# PCB-BI8-1x8SC3.net
KiCad netlist of a schematic drawn in EAGLE
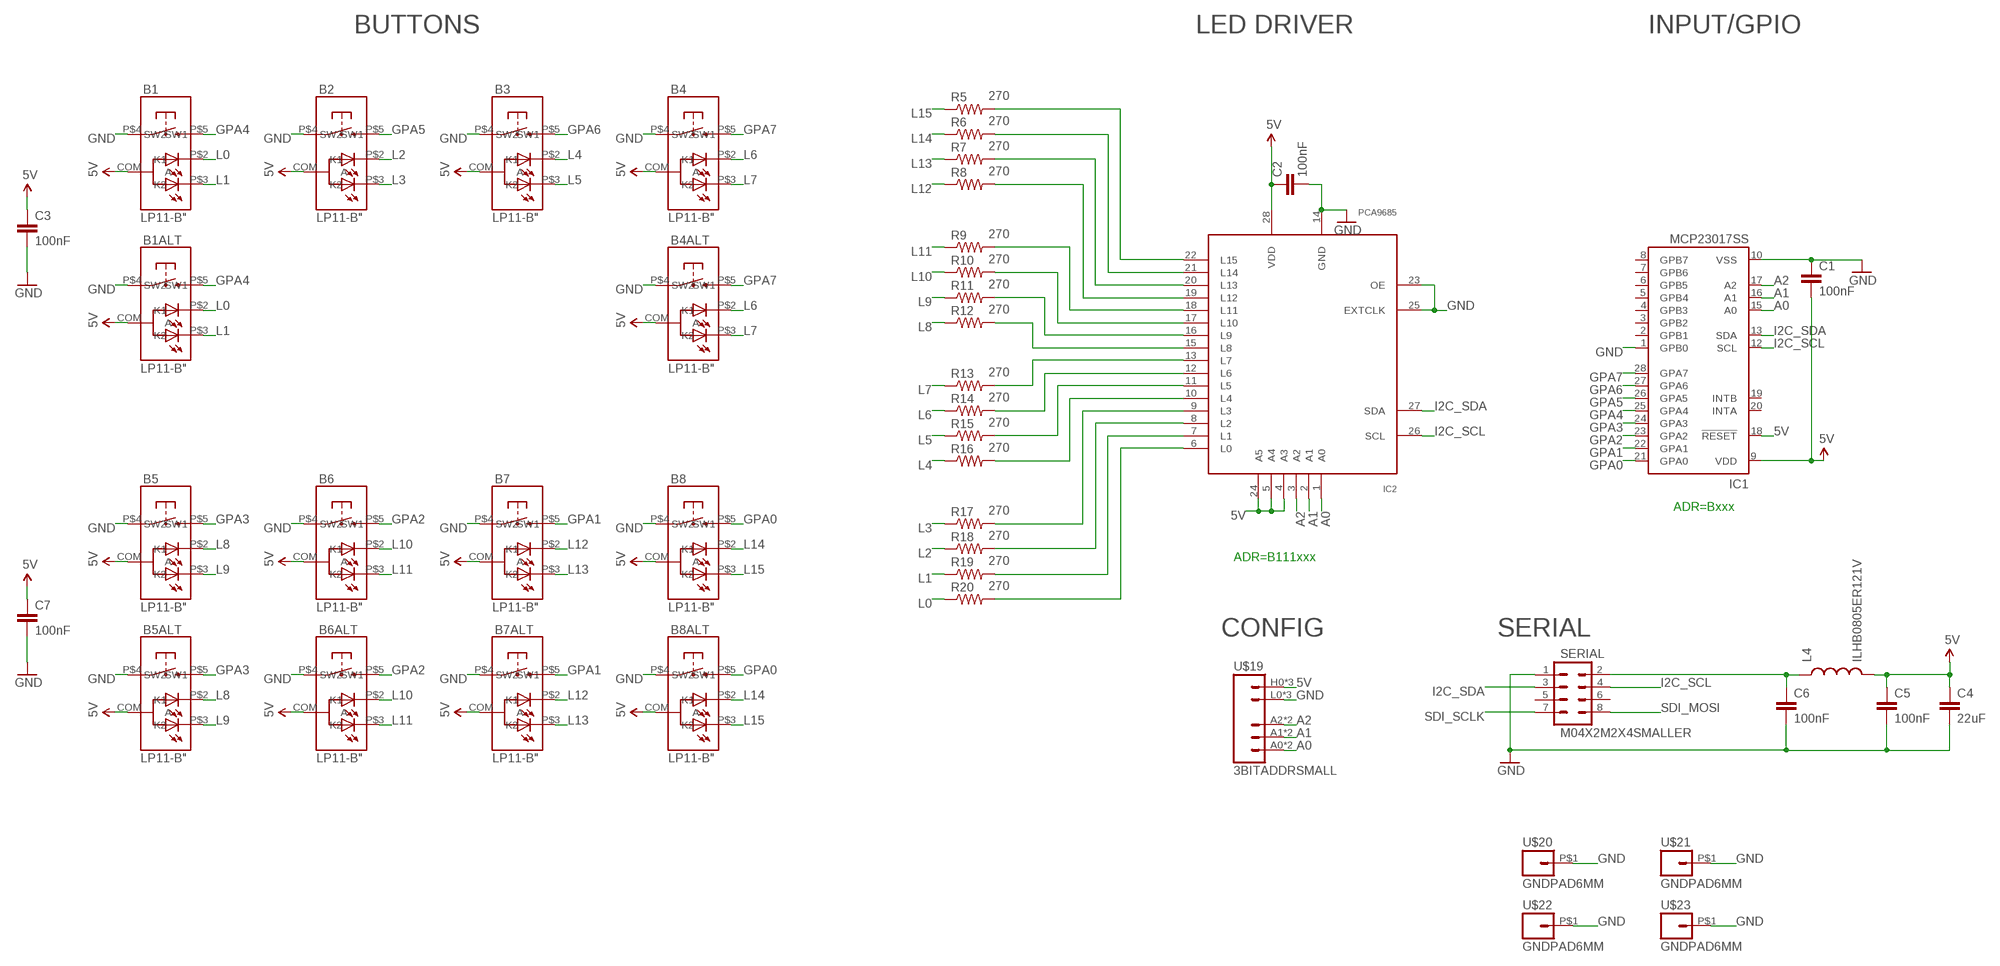
[diagram p0: schematic, sheet 1]

(export (version "E")
  (design (tool "Eeschema 10.0.6"))
  (components
    (comp (ref "B1")
      (value "LP11-B\"")
      (footprint "eagle-import:LP11")
      (libsource (lib "eagle-import") (part "LP11-B{dblquote}"))
    )
    (comp (ref "B1ALT")
      (value "LP11-B\"")
      (footprint "eagle-import:LP11")
      (libsource (lib "eagle-import") (part "LP11-B{dblquote}"))
    )
    (comp (ref "B2")
      (value "LP11-B\"")
      (footprint "eagle-import:LP11")
      (libsource (lib "eagle-import") (part "LP11-B{dblquote}"))
    )
    (comp (ref "B3")
      (value "LP11-B\"")
      (footprint "eagle-import:LP11")
      (libsource (lib "eagle-import") (part "LP11-B{dblquote}"))
    )
    (comp (ref "B4")
      (value "LP11-B\"")
      (footprint "eagle-import:LP11")
      (libsource (lib "eagle-import") (part "LP11-B{dblquote}"))
    )
    (comp (ref "B4ALT")
      (value "LP11-B\"")
      (footprint "eagle-import:LP11")
      (libsource (lib "eagle-import") (part "LP11-B{dblquote}"))
    )
    (comp (ref "B5")
      (value "LP11-B\"")
      (footprint "eagle-import:LP11")
      (libsource (lib "eagle-import") (part "LP11-B{dblquote}"))
    )
    (comp (ref "B5ALT")
      (value "LP11-B\"")
      (footprint "eagle-import:LP11")
      (libsource (lib "eagle-import") (part "LP11-B{dblquote}"))
    )
    (comp (ref "B6")
      (value "LP11-B\"")
      (footprint "eagle-import:LP11")
      (libsource (lib "eagle-import") (part "LP11-B{dblquote}"))
    )
    (comp (ref "B6ALT")
      (value "LP11-B\"")
      (footprint "eagle-import:LP11")
      (libsource (lib "eagle-import") (part "LP11-B{dblquote}"))
    )
    (comp (ref "B7")
      (value "LP11-B\"")
      (footprint "eagle-import:LP11")
      (libsource (lib "eagle-import") (part "LP11-B{dblquote}"))
    )
    (comp (ref "B7ALT")
      (value "LP11-B\"")
      (footprint "eagle-import:LP11")
      (libsource (lib "eagle-import") (part "LP11-B{dblquote}"))
    )
    (comp (ref "B8")
      (value "LP11-B\"")
      (footprint "eagle-import:LP11")
      (libsource (lib "eagle-import") (part "LP11-B{dblquote}"))
    )
    (comp (ref "B8ALT")
      (value "LP11-B\"")
      (footprint "eagle-import:LP11")
      (libsource (lib "eagle-import") (part "LP11-B{dblquote}"))
    )
    (comp (ref "C1")
      (value "100nF")
      (footprint "eagle-import:0603-CAP")
      (libsource (lib "eagle-import") (part "CAP0603-CAP"))
    )
    (comp (ref "C2")
      (value "100nF")
      (footprint "eagle-import:0603-CAP")
      (libsource (lib "eagle-import") (part "CAP0603-CAP"))
    )
    (comp (ref "C3")
      (value "100nF")
      (footprint "eagle-import:0603-CAP")
      (libsource (lib "eagle-import") (part "CAP0603-CAP"))
    )
    (comp (ref "C4")
      (value "22uF")
      (footprint "eagle-import:0805")
      (libsource (lib "eagle-import") (part "CAP0805"))
    )
    (comp (ref "C5")
      (value "100nF")
      (footprint "eagle-import:0603-CAP")
      (libsource (lib "eagle-import") (part "CAP0603-CAP"))
    )
    (comp (ref "C6")
      (value "100nF")
      (footprint "eagle-import:0603-CAP")
      (libsource (lib "eagle-import") (part "CAP0603-CAP"))
    )
    (comp (ref "C7")
      (value "100nF")
      (footprint "eagle-import:0603-CAP")
      (libsource (lib "eagle-import") (part "CAP0603-CAP"))
    )
    (comp (ref "IC1")
      (value "MCP23017SS")
      (footprint "eagle-import:SSOP28")
      (fields
        (field (name "MF") "MICROCHIP")
        (field (name "MPN") "MCP23017-E/SS")
        (field (name "MPN_1") "MCP23017-E/SS")
        (field (name "OC_FARNELL") "1467674")
        (field (name "OC_NEWARK") "31K2960")
      )
      (libsource (lib "eagle-import") (part "MCP23017SS"))
    )
    (comp (ref "IC2")
      (value "PCA9685")
      (footprint "eagle-import:TSSOP28")
      (libsource (lib "eagle-import") (part "PCA9685"))
    )
    (comp (ref "L4")
      (value "ILHB0805ER121V")
      (footprint "eagle-import:0805")
      (libsource (lib "eagle-import") (part "INDUCTOR0805"))
    )
    (comp (ref "R5")
      (value "270")
      (footprint "eagle-import:0603-RES")
      (libsource (lib "eagle-import") (part "RESISTOR0603-RES"))
    )
    (comp (ref "R6")
      (value "270")
      (footprint "eagle-import:0603-RES")
      (libsource (lib "eagle-import") (part "RESISTOR0603-RES"))
    )
    (comp (ref "R7")
      (value "270")
      (footprint "eagle-import:0603-RES")
      (libsource (lib "eagle-import") (part "RESISTOR0603-RES"))
    )
    (comp (ref "R8")
      (value "270")
      (footprint "eagle-import:0603-RES")
      (libsource (lib "eagle-import") (part "RESISTOR0603-RES"))
    )
    (comp (ref "R9")
      (value "270")
      (footprint "eagle-import:0603-RES")
      (libsource (lib "eagle-import") (part "RESISTOR0603-RES"))
    )
    (comp (ref "R10")
      (value "270")
      (footprint "eagle-import:0603-RES")
      (libsource (lib "eagle-import") (part "RESISTOR0603-RES"))
    )
    (comp (ref "R11")
      (value "270")
      (footprint "eagle-import:0603-RES")
      (libsource (lib "eagle-import") (part "RESISTOR0603-RES"))
    )
    (comp (ref "R12")
      (value "270")
      (footprint "eagle-import:0603-RES")
      (libsource (lib "eagle-import") (part "RESISTOR0603-RES"))
    )
    (comp (ref "R13")
      (value "270")
      (footprint "eagle-import:0603-RES")
      (libsource (lib "eagle-import") (part "RESISTOR0603-RES"))
    )
    (comp (ref "R14")
      (value "270")
      (footprint "eagle-import:0603-RES")
      (libsource (lib "eagle-import") (part "RESISTOR0603-RES"))
    )
    (comp (ref "R15")
      (value "270")
      (footprint "eagle-import:0603-RES")
      (libsource (lib "eagle-import") (part "RESISTOR0603-RES"))
    )
    (comp (ref "R16")
      (value "270")
      (footprint "eagle-import:0603-RES")
      (libsource (lib "eagle-import") (part "RESISTOR0603-RES"))
    )
    (comp (ref "R17")
      (value "270")
      (footprint "eagle-import:0603-RES")
      (libsource (lib "eagle-import") (part "RESISTOR0603-RES"))
    )
    (comp (ref "R18")
      (value "270")
      (footprint "eagle-import:0603-RES")
      (libsource (lib "eagle-import") (part "RESISTOR0603-RES"))
    )
    (comp (ref "R19")
      (value "270")
      (footprint "eagle-import:0603-RES")
      (libsource (lib "eagle-import") (part "RESISTOR0603-RES"))
    )
    (comp (ref "R20")
      (value "270")
      (footprint "eagle-import:0603-RES")
      (libsource (lib "eagle-import") (part "RESISTOR0603-RES"))
    )
    (comp (ref "SERIAL")
      (value "M04X2M2X4SMALLER")
      (footprint "eagle-import:M2X4SMALLER")
      (libsource (lib "eagle-import") (part "M04X2M2X4SMALLER"))
    )
    (comp (ref "U$19")
      (value "3BITADDRSMALL")
      (footprint "eagle-import:3BITADDR_SMALL")
      (libsource (lib "eagle-import") (part "3BITADDRSMALL"))
    )
    (comp (ref "U$20")
      (value "GNDPAD6MM")
      (footprint "eagle-import:3.2MMPAD6MM")
      (libsource (lib "eagle-import") (part "GNDPAD6MM"))
    )
    (comp (ref "U$21")
      (value "GNDPAD6MM")
      (footprint "eagle-import:3.2MMPAD6MM")
      (libsource (lib "eagle-import") (part "GNDPAD6MM"))
    )
    (comp (ref "U$22")
      (value "GNDPAD6MM")
      (footprint "eagle-import:3.2MMPAD6MM")
      (libsource (lib "eagle-import") (part "GNDPAD6MM"))
    )
    (comp (ref "U$23")
      (value "GNDPAD6MM")
      (footprint "eagle-import:3.2MMPAD6MM")
      (libsource (lib "eagle-import") (part "GNDPAD6MM"))
    )
  )
  (nets
    (net (code "1") (name "/A0") (class "Default")
      (node (ref "IC1") (pin "15") (pinfunction "A0_15") (pintype "input"))
      (node (ref "IC2") (pin "1") (pinfunction "A0_1") (pintype "input"))
      (node (ref "U$19") (pin "A0") (pinfunction "A0_A0") (pintype "passive"))
      (node (ref "U$19") (pin "AS0") (pinfunction "A0_AS0") (pintype "passive"))
    )
    (net (code "2") (name "/A1") (class "Default")
      (node (ref "IC1") (pin "16") (pinfunction "A1_16") (pintype "input"))
      (node (ref "IC2") (pin "2") (pinfunction "A1_2") (pintype "input"))
      (node (ref "U$19") (pin "A1") (pinfunction "A1_A1") (pintype "passive"))
      (node (ref "U$19") (pin "AS1") (pinfunction "A1_AS1") (pintype "passive"))
    )
    (net (code "3") (name "/A2") (class "Default")
      (node (ref "IC1") (pin "17") (pinfunction "A2_17") (pintype "input"))
      (node (ref "IC2") (pin "3") (pinfunction "A2_3") (pintype "input"))
      (node (ref "U$19") (pin "A2") (pinfunction "A2_A2") (pintype "passive"))
      (node (ref "U$19") (pin "AS2") (pinfunction "A2_AS2") (pintype "passive"))
    )
    (net (code "4") (name "/GPA0") (class "Default")
      (node (ref "B8") (pin "P$5") (pinfunction "SW2_P$5") (pintype "bidirectional"))
      (node (ref "B8ALT") (pin "P$5") (pinfunction "SW2_P$5") (pintype "bidirectional"))
      (node (ref "IC1") (pin "21") (pinfunction "GPA0_21") (pintype "bidirectional"))
    )
    (net (code "5") (name "/GPA1") (class "Default")
      (node (ref "B7") (pin "P$5") (pinfunction "SW2_P$5") (pintype "bidirectional"))
      (node (ref "B7ALT") (pin "P$5") (pinfunction "SW2_P$5") (pintype "bidirectional"))
      (node (ref "IC1") (pin "22") (pinfunction "GPA1_22") (pintype "bidirectional"))
    )
    (net (code "6") (name "/GPA2") (class "Default")
      (node (ref "B6") (pin "P$5") (pinfunction "SW2_P$5") (pintype "bidirectional"))
      (node (ref "B6ALT") (pin "P$5") (pinfunction "SW2_P$5") (pintype "bidirectional"))
      (node (ref "IC1") (pin "23") (pinfunction "GPA2_23") (pintype "bidirectional"))
    )
    (net (code "7") (name "/GPA3") (class "Default")
      (node (ref "B5") (pin "P$5") (pinfunction "SW2_P$5") (pintype "bidirectional"))
      (node (ref "B5ALT") (pin "P$5") (pinfunction "SW2_P$5") (pintype "bidirectional"))
      (node (ref "IC1") (pin "24") (pinfunction "GPA3_24") (pintype "bidirectional"))
    )
    (net (code "8") (name "/GPA4") (class "Default")
      (node (ref "B1") (pin "P$5") (pinfunction "SW2_P$5") (pintype "bidirectional"))
      (node (ref "B1ALT") (pin "P$5") (pinfunction "SW2_P$5") (pintype "bidirectional"))
      (node (ref "IC1") (pin "25") (pinfunction "GPA4_25") (pintype "bidirectional"))
    )
    (net (code "9") (name "/GPA5") (class "Default")
      (node (ref "B2") (pin "P$5") (pinfunction "SW2_P$5") (pintype "bidirectional"))
      (node (ref "IC1") (pin "26") (pinfunction "GPA5_26") (pintype "bidirectional"))
    )
    (net (code "10") (name "/GPA6") (class "Default")
      (node (ref "B3") (pin "P$5") (pinfunction "SW2_P$5") (pintype "bidirectional"))
      (node (ref "IC1") (pin "27") (pinfunction "GPA6_27") (pintype "bidirectional"))
    )
    (net (code "11") (name "/GPA7") (class "Default")
      (node (ref "B4") (pin "P$5") (pinfunction "SW2_P$5") (pintype "bidirectional"))
      (node (ref "B4ALT") (pin "P$5") (pinfunction "SW2_P$5") (pintype "bidirectional"))
      (node (ref "IC1") (pin "28") (pinfunction "GPA7_28") (pintype "bidirectional"))
    )
    (net (code "12") (name "/I2C_SCL") (class "Default")
      (node (ref "IC1") (pin "12") (pinfunction "SCL_12") (pintype "input"))
      (node (ref "IC2") (pin "26") (pinfunction "SCL_26") (pintype "input"))
      (node (ref "SERIAL") (pin "4") (pinfunction "4_4") (pintype "passive"))
    )
    (net (code "13") (name "/I2C_SDA") (class "Default")
      (node (ref "IC1") (pin "13") (pinfunction "SDA_13") (pintype "bidirectional"))
      (node (ref "IC2") (pin "27") (pinfunction "SDA_27") (pintype "input"))
      (node (ref "SERIAL") (pin "3") (pinfunction "3_3") (pintype "passive"))
    )
    (net (code "14") (name "/L0") (class "Default")
      (node (ref "B1") (pin "P$2") (pinfunction "K1_P$2") (pintype "bidirectional"))
      (node (ref "B1ALT") (pin "P$2") (pinfunction "K1_P$2") (pintype "bidirectional"))
      (node (ref "R20") (pin "1") (pinfunction "1_1") (pintype "passive"))
    )
    (net (code "15") (name "/L1") (class "Default")
      (node (ref "B1") (pin "P$3") (pinfunction "K2_P$3") (pintype "bidirectional"))
      (node (ref "B1ALT") (pin "P$3") (pinfunction "K2_P$3") (pintype "bidirectional"))
      (node (ref "R19") (pin "1") (pinfunction "1_1") (pintype "passive"))
    )
    (net (code "16") (name "/L2") (class "Default")
      (node (ref "B2") (pin "P$2") (pinfunction "K1_P$2") (pintype "bidirectional"))
      (node (ref "R18") (pin "1") (pinfunction "1_1") (pintype "passive"))
    )
    (net (code "17") (name "/L3") (class "Default")
      (node (ref "B2") (pin "P$3") (pinfunction "K2_P$3") (pintype "bidirectional"))
      (node (ref "R17") (pin "1") (pinfunction "1_1") (pintype "passive"))
    )
    (net (code "18") (name "/L4") (class "Default")
      (node (ref "B3") (pin "P$2") (pinfunction "K1_P$2") (pintype "bidirectional"))
      (node (ref "R16") (pin "1") (pinfunction "1_1") (pintype "passive"))
    )
    (net (code "19") (name "/L5") (class "Default")
      (node (ref "B3") (pin "P$3") (pinfunction "K2_P$3") (pintype "bidirectional"))
      (node (ref "R15") (pin "1") (pinfunction "1_1") (pintype "passive"))
    )
    (net (code "20") (name "/L6") (class "Default")
      (node (ref "B4") (pin "P$2") (pinfunction "K1_P$2") (pintype "bidirectional"))
      (node (ref "B4ALT") (pin "P$2") (pinfunction "K1_P$2") (pintype "bidirectional"))
      (node (ref "R14") (pin "1") (pinfunction "1_1") (pintype "passive"))
    )
    (net (code "21") (name "/L7") (class "Default")
      (node (ref "B4") (pin "P$3") (pinfunction "K2_P$3") (pintype "bidirectional"))
      (node (ref "B4ALT") (pin "P$3") (pinfunction "K2_P$3") (pintype "bidirectional"))
      (node (ref "R13") (pin "1") (pinfunction "1_1") (pintype "passive"))
    )
    (net (code "22") (name "/L8") (class "Default")
      (node (ref "B5") (pin "P$2") (pinfunction "K1_P$2") (pintype "bidirectional"))
      (node (ref "B5ALT") (pin "P$2") (pinfunction "K1_P$2") (pintype "bidirectional"))
      (node (ref "R12") (pin "1") (pinfunction "1_1") (pintype "passive"))
    )
    (net (code "23") (name "/L9") (class "Default")
      (node (ref "B5") (pin "P$3") (pinfunction "K2_P$3") (pintype "bidirectional"))
      (node (ref "B5ALT") (pin "P$3") (pinfunction "K2_P$3") (pintype "bidirectional"))
      (node (ref "R11") (pin "1") (pinfunction "1_1") (pintype "passive"))
    )
    (net (code "24") (name "/L10") (class "Default")
      (node (ref "B6") (pin "P$2") (pinfunction "K1_P$2") (pintype "bidirectional"))
      (node (ref "B6ALT") (pin "P$2") (pinfunction "K1_P$2") (pintype "bidirectional"))
      (node (ref "R10") (pin "1") (pinfunction "1_1") (pintype "passive"))
    )
    (net (code "25") (name "/L11") (class "Default")
      (node (ref "B6") (pin "P$3") (pinfunction "K2_P$3") (pintype "bidirectional"))
      (node (ref "B6ALT") (pin "P$3") (pinfunction "K2_P$3") (pintype "bidirectional"))
      (node (ref "R9") (pin "1") (pinfunction "1_1") (pintype "passive"))
    )
    (net (code "26") (name "/L12") (class "Default")
      (node (ref "B7") (pin "P$2") (pinfunction "K1_P$2") (pintype "bidirectional"))
      (node (ref "B7ALT") (pin "P$2") (pinfunction "K1_P$2") (pintype "bidirectional"))
      (node (ref "R8") (pin "1") (pinfunction "1_1") (pintype "passive"))
    )
    (net (code "27") (name "/L13") (class "Default")
      (node (ref "B7") (pin "P$3") (pinfunction "K2_P$3") (pintype "bidirectional"))
      (node (ref "B7ALT") (pin "P$3") (pinfunction "K2_P$3") (pintype "bidirectional"))
      (node (ref "R7") (pin "1") (pinfunction "1_1") (pintype "passive"))
    )
    (net (code "28") (name "/L14") (class "Default")
      (node (ref "B8") (pin "P$2") (pinfunction "K1_P$2") (pintype "bidirectional"))
      (node (ref "B8ALT") (pin "P$2") (pinfunction "K1_P$2") (pintype "bidirectional"))
      (node (ref "R6") (pin "1") (pinfunction "1_1") (pintype "passive"))
    )
    (net (code "29") (name "/L15") (class "Default")
      (node (ref "B8") (pin "P$3") (pinfunction "K2_P$3") (pintype "bidirectional"))
      (node (ref "B8ALT") (pin "P$3") (pinfunction "K2_P$3") (pintype "bidirectional"))
      (node (ref "R5") (pin "1") (pinfunction "1_1") (pintype "passive"))
    )
    (net (code "30") (name "/SDI_MOSI") (class "Default")
      (node (ref "SERIAL") (pin "8") (pinfunction "8_8") (pintype "passive"))
    )
    (net (code "31") (name "/SDI_SCLK") (class "Default")
      (node (ref "SERIAL") (pin "7") (pinfunction "7_7") (pintype "passive"))
    )
    (net (code "32") (name "5V") (class "Default")
      (node (ref "B1") (pin "COM") (pinfunction "A_COM") (pintype "bidirectional"))
      (node (ref "B1ALT") (pin "COM") (pinfunction "A_COM") (pintype "bidirectional"))
      (node (ref "B2") (pin "COM") (pinfunction "A_COM") (pintype "bidirectional"))
      (node (ref "B3") (pin "COM") (pinfunction "A_COM") (pintype "bidirectional"))
      (node (ref "B4") (pin "COM") (pinfunction "A_COM") (pintype "bidirectional"))
      (node (ref "B4ALT") (pin "COM") (pinfunction "A_COM") (pintype "bidirectional"))
      (node (ref "B5") (pin "COM") (pinfunction "A_COM") (pintype "bidirectional"))
      (node (ref "B5ALT") (pin "COM") (pinfunction "A_COM") (pintype "bidirectional"))
      (node (ref "B6") (pin "COM") (pinfunction "A_COM") (pintype "bidirectional"))
      (node (ref "B6ALT") (pin "COM") (pinfunction "A_COM") (pintype "bidirectional"))
      (node (ref "B7") (pin "COM") (pinfunction "A_COM") (pintype "bidirectional"))
      (node (ref "B7ALT") (pin "COM") (pinfunction "A_COM") (pintype "bidirectional"))
      (node (ref "B8") (pin "COM") (pinfunction "A_COM") (pintype "bidirectional"))
      (node (ref "B8ALT") (pin "COM") (pinfunction "A_COM") (pintype "bidirectional"))
      (node (ref "C1") (pin "2") (pinfunction "2_2") (pintype "passive"))
      (node (ref "C2") (pin "1") (pinfunction "1_1") (pintype "passive"))
      (node (ref "C3") (pin "1") (pinfunction "1_1") (pintype "passive"))
      (node (ref "C4") (pin "1") (pinfunction "1_1") (pintype "passive"))
      (node (ref "C5") (pin "1") (pinfunction "1_1") (pintype "passive"))
      (node (ref "C7") (pin "1") (pinfunction "1_1") (pintype "passive"))
      (node (ref "IC1") (pin "18") (pinfunction "~{RESET}_18") (pintype "input"))
      (node (ref "IC1") (pin "9") (pinfunction "VDD_9") (pintype "power_in"))
      (node (ref "IC2") (pin "24") (pinfunction "A5_24") (pintype "input"))
      (node (ref "IC2") (pin "28") (pinfunction "VDD_28") (pintype "power_in"))
      (node (ref "IC2") (pin "4") (pinfunction "A3_4") (pintype "input"))
      (node (ref "IC2") (pin "5") (pinfunction "A4_5") (pintype "input"))
      (node (ref "L4") (pin "2") (pinfunction "2_2") (pintype "passive"))
      (node (ref "U$19") (pin "H0") (pinfunction "VCC_H0") (pintype "passive"))
      (node (ref "U$19") (pin "H1") (pinfunction "VCC_H1") (pintype "passive"))
      (node (ref "U$19") (pin "H2") (pinfunction "VCC_H2") (pintype "passive"))
    )
    (net (code "33") (name "GND") (class "Default")
      (node (ref "B1") (pin "P$4") (pinfunction "SW1_P$4") (pintype "bidirectional"))
      (node (ref "B1ALT") (pin "P$4") (pinfunction "SW1_P$4") (pintype "bidirectional"))
      (node (ref "B2") (pin "P$4") (pinfunction "SW1_P$4") (pintype "bidirectional"))
      (node (ref "B3") (pin "P$4") (pinfunction "SW1_P$4") (pintype "bidirectional"))
      (node (ref "B4") (pin "P$4") (pinfunction "SW1_P$4") (pintype "bidirectional"))
      (node (ref "B4ALT") (pin "P$4") (pinfunction "SW1_P$4") (pintype "bidirectional"))
      (node (ref "B5") (pin "P$4") (pinfunction "SW1_P$4") (pintype "bidirectional"))
      (node (ref "B5ALT") (pin "P$4") (pinfunction "SW1_P$4") (pintype "bidirectional"))
      (node (ref "B6") (pin "P$4") (pinfunction "SW1_P$4") (pintype "bidirectional"))
      (node (ref "B6ALT") (pin "P$4") (pinfunction "SW1_P$4") (pintype "bidirectional"))
      (node (ref "B7") (pin "P$4") (pinfunction "SW1_P$4") (pintype "bidirectional"))
      (node (ref "B7ALT") (pin "P$4") (pinfunction "SW1_P$4") (pintype "bidirectional"))
      (node (ref "B8") (pin "P$4") (pinfunction "SW1_P$4") (pintype "bidirectional"))
      (node (ref "B8ALT") (pin "P$4") (pinfunction "SW1_P$4") (pintype "bidirectional"))
      (node (ref "C1") (pin "1") (pinfunction "1_1") (pintype "passive"))
      (node (ref "C2") (pin "2") (pinfunction "2_2") (pintype "passive"))
      (node (ref "C3") (pin "2") (pinfunction "2_2") (pintype "passive"))
      (node (ref "C4") (pin "2") (pinfunction "2_2") (pintype "passive"))
      (node (ref "C5") (pin "2") (pinfunction "2_2") (pintype "passive"))
      (node (ref "C6") (pin "2") (pinfunction "2_2") (pintype "passive"))
      (node (ref "C7") (pin "2") (pinfunction "2_2") (pintype "passive"))
      (node (ref "IC1") (pin "1") (pinfunction "GPB0_1") (pintype "bidirectional"))
      (node (ref "IC1") (pin "10") (pinfunction "VSS_10") (pintype "power_in"))
      (node (ref "IC2") (pin "14") (pinfunction "GND_14") (pintype "power_in"))
      (node (ref "IC2") (pin "23") (pinfunction "OE_23") (pintype "input"))
      (node (ref "IC2") (pin "25") (pinfunction "EXTCLK_25") (pintype "input"))
      (node (ref "SERIAL") (pin "1") (pinfunction "1_1") (pintype "passive"))
      (node (ref "U$19") (pin "L0") (pinfunction "GND_L0") (pintype "passive"))
      (node (ref "U$19") (pin "L1") (pinfunction "GND_L1") (pintype "passive"))
      (node (ref "U$19") (pin "L2") (pinfunction "GND_L2") (pintype "passive"))
      (node (ref "U$20") (pin "P$1") (pinfunction "1_P$1") (pintype "passive"))
      (node (ref "U$21") (pin "P$1") (pinfunction "1_P$1") (pintype "passive"))
      (node (ref "U$22") (pin "P$1") (pinfunction "1_P$1") (pintype "passive"))
      (node (ref "U$23") (pin "P$1") (pinfunction "1_P$1") (pintype "passive"))
    )
    (net (code "34") (name "Net-(C6-Pad1)") (class "Default")
      (node (ref "C6") (pin "1") (pinfunction "1_1") (pintype "passive"))
      (node (ref "L4") (pin "1") (pinfunction "1_1") (pintype "passive"))
      (node (ref "SERIAL") (pin "2") (pinfunction "2_2") (pintype "passive"))
    )
    (net (code "35") (name "Net-(IC2-L0)") (class "Default")
      (node (ref "IC2") (pin "6") (pinfunction "L0_6") (pintype "output"))
      (node (ref "R20") (pin "2") (pinfunction "2_2") (pintype "passive"))
    )
    (net (code "36") (name "Net-(IC2-L1)") (class "Default")
      (node (ref "IC2") (pin "7") (pinfunction "L1_7") (pintype "output"))
      (node (ref "R19") (pin "2") (pinfunction "2_2") (pintype "passive"))
    )
    (net (code "37") (name "Net-(IC2-L2)") (class "Default")
      (node (ref "IC2") (pin "8") (pinfunction "L2_8") (pintype "output"))
      (node (ref "R18") (pin "2") (pinfunction "2_2") (pintype "passive"))
    )
    (net (code "38") (name "Net-(IC2-L3)") (class "Default")
      (node (ref "IC2") (pin "9") (pinfunction "L3_9") (pintype "output"))
      (node (ref "R17") (pin "2") (pinfunction "2_2") (pintype "passive"))
    )
    (net (code "39") (name "Net-(IC2-L4)") (class "Default")
      (node (ref "IC2") (pin "10") (pinfunction "L4_10") (pintype "output"))
      (node (ref "R16") (pin "2") (pinfunction "2_2") (pintype "passive"))
    )
    (net (code "40") (name "Net-(IC2-L5)") (class "Default")
      (node (ref "IC2") (pin "11") (pinfunction "L5_11") (pintype "output"))
      (node (ref "R15") (pin "2") (pinfunction "2_2") (pintype "passive"))
    )
    (net (code "41") (name "Net-(IC2-L6)") (class "Default")
      (node (ref "IC2") (pin "12") (pinfunction "L6_12") (pintype "output"))
      (node (ref "R14") (pin "2") (pinfunction "2_2") (pintype "passive"))
    )
    (net (code "42") (name "Net-(IC2-L7)") (class "Default")
      (node (ref "IC2") (pin "13") (pinfunction "L7_13") (pintype "output"))
      (node (ref "R13") (pin "2") (pinfunction "2_2") (pintype "passive"))
    )
    (net (code "43") (name "Net-(IC2-L8)") (class "Default")
      (node (ref "IC2") (pin "15") (pinfunction "L8_15") (pintype "output"))
      (node (ref "R12") (pin "2") (pinfunction "2_2") (pintype "passive"))
    )
    (net (code "44") (name "Net-(IC2-L9)") (class "Default")
      (node (ref "IC2") (pin "16") (pinfunction "L9_16") (pintype "output"))
      (node (ref "R11") (pin "2") (pinfunction "2_2") (pintype "passive"))
    )
    (net (code "45") (name "Net-(IC2-L10)") (class "Default")
      (node (ref "IC2") (pin "17") (pinfunction "L10_17") (pintype "output"))
      (node (ref "R10") (pin "2") (pinfunction "2_2") (pintype "passive"))
    )
    (net (code "46") (name "Net-(IC2-L11)") (class "Default")
      (node (ref "IC2") (pin "18") (pinfunction "L11_18") (pintype "output"))
      (node (ref "R9") (pin "2") (pinfunction "2_2") (pintype "passive"))
    )
    (net (code "47") (name "Net-(IC2-L12)") (class "Default")
      (node (ref "IC2") (pin "19") (pinfunction "L12_19") (pintype "output"))
      (node (ref "R8") (pin "2") (pinfunction "2_2") (pintype "passive"))
    )
    (net (code "48") (name "Net-(IC2-L13)") (class "Default")
      (node (ref "IC2") (pin "20") (pinfunction "L13_20") (pintype "output"))
      (node (ref "R7") (pin "2") (pinfunction "2_2") (pintype "passive"))
    )
    (net (code "49") (name "Net-(IC2-L14)") (class "Default")
      (node (ref "IC2") (pin "21") (pinfunction "L14_21") (pintype "output"))
      (node (ref "R6") (pin "2") (pinfunction "2_2") (pintype "passive"))
    )
    (net (code "50") (name "Net-(IC2-L15)") (class "Default")
      (node (ref "IC2") (pin "22") (pinfunction "L15_22") (pintype "output"))
      (node (ref "R5") (pin "2") (pinfunction "2_2") (pintype "passive"))
    )
    (net (code "51") (name "unconnected-(IC1-GPB1-Pad2)") (class "Default")
      (node (ref "IC1") (pin "2") (pinfunction "GPB1_2") (pintype "bidirectional"))
    )
    (net (code "52") (name "unconnected-(IC1-GPB2-Pad3)") (class "Default")
      (node (ref "IC1") (pin "3") (pinfunction "GPB2_3") (pintype "bidirectional"))
    )
    (net (code "53") (name "unconnected-(IC1-GPB3-Pad4)") (class "Default")
      (node (ref "IC1") (pin "4") (pinfunction "GPB3_4") (pintype "bidirectional"))
    )
    (net (code "54") (name "unconnected-(IC1-GPB4-Pad5)") (class "Default")
      (node (ref "IC1") (pin "5") (pinfunction "GPB4_5") (pintype "bidirectional"))
    )
    (net (code "55") (name "unconnected-(IC1-GPB5-Pad6)") (class "Default")
      (node (ref "IC1") (pin "6") (pinfunction "GPB5_6") (pintype "bidirectional"))
    )
    (net (code "56") (name "unconnected-(IC1-GPB6-Pad7)") (class "Default")
      (node (ref "IC1") (pin "7") (pinfunction "GPB6_7") (pintype "bidirectional"))
    )
    (net (code "57") (name "unconnected-(IC1-GPB7-Pad8)") (class "Default")
      (node (ref "IC1") (pin "8") (pinfunction "GPB7_8") (pintype "bidirectional"))
    )
    (net (code "58") (name "unconnected-(IC1-INTA-Pad20)") (class "Default")
      (node (ref "IC1") (pin "20") (pinfunction "INTA_20") (pintype "output"))
    )
    (net (code "59") (name "unconnected-(IC1-INTB-Pad19)") (class "Default")
      (node (ref "IC1") (pin "19") (pinfunction "INTB_19") (pintype "output"))
    )
    (net (code "60") (name "unconnected-(SERIAL-Pad5)") (class "Default")
      (node (ref "SERIAL") (pin "5") (pinfunction "5_5") (pintype "passive"))
    )
    (net (code "61") (name "unconnected-(SERIAL-Pad6)") (class "Default")
      (node (ref "SERIAL") (pin "6") (pinfunction "6_6") (pintype "passive"))
    )
  )
)
